# Core-ProMini.net
KiCad netlist of a schematic drawn in EAGLE
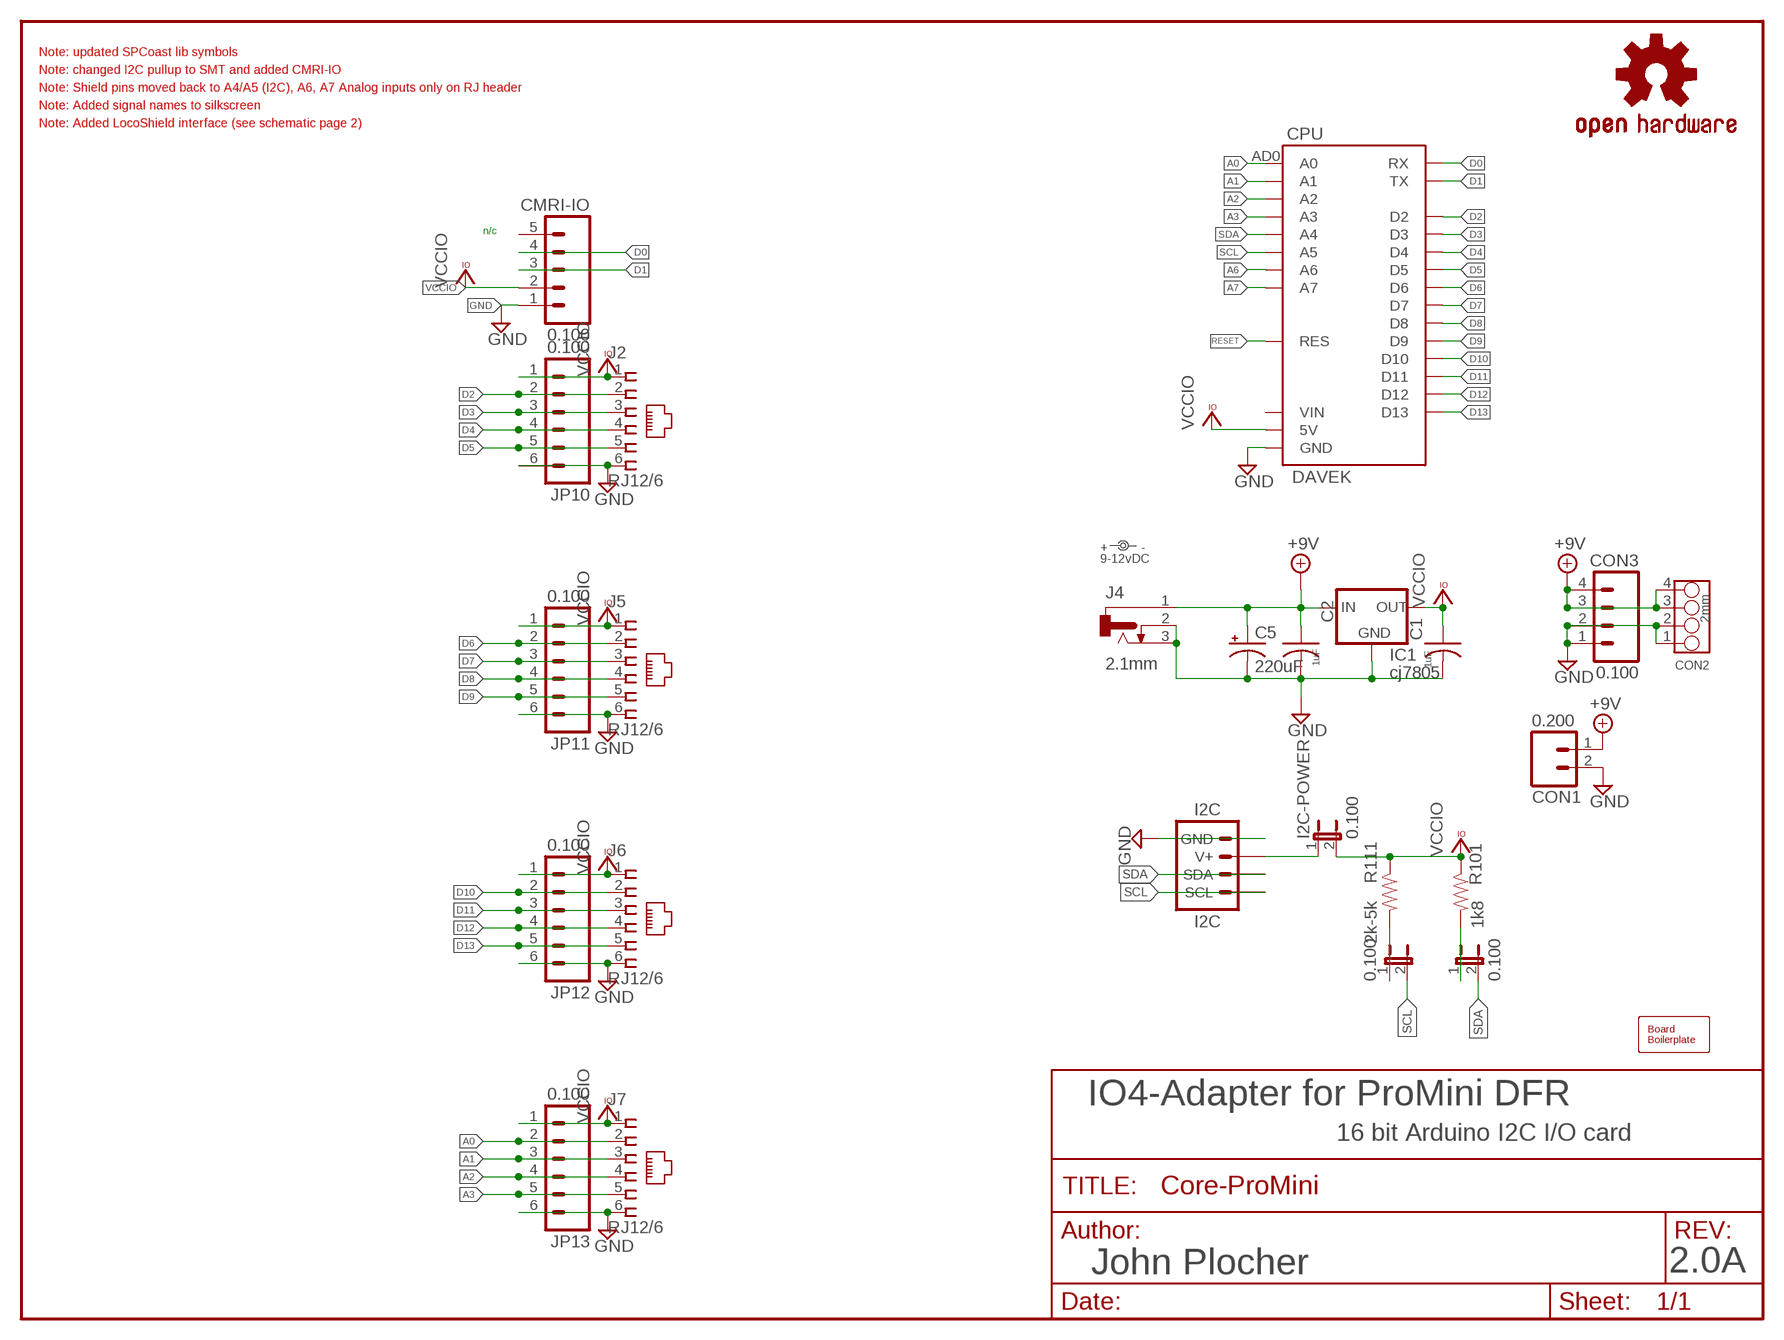
[diagram p0: schematic, sheet 1]

(export (version "E")
  (design (tool "Eeschema 10.0.6"))
  (components
    (comp (ref "BOARD")
      (value "BOARD")
      (footprint "eagle-import:BOARD-DINRAIL-3.17INX10CM")
      (libsource (lib "eagle-import") (part "BOARD80X100"))
    )
    (comp (ref "C1")
      (value "1uF")
      (footprint "eagle-import:0603-CAP")
      (libsource (lib "eagle-import") (part "CAP0603"))
    )
    (comp (ref "C2")
      (value "1uF")
      (footprint "eagle-import:0603-CAP")
      (libsource (lib "eagle-import") (part "CAP0603"))
    )
    (comp (ref "C5")
      (value "220uF")
      (footprint "eagle-import:0810-CAP")
      (libsource (lib "eagle-import") (part "CAP-POL0810"))
    )
    (comp (ref "CMRI-IO")
      (value "0.100")
      (footprint "eagle-import:1X05-CMRI-IO")
      (libsource (lib "eagle-import") (part "CONNECTOR-M05CMRI"))
    )
    (comp (ref "CON1")
      (value "0.200")
      (footprint "eagle-import:MSTB2")
      (libsource (lib "eagle-import") (part "CONNECTOR-M02508-LOCK"))
    )
    (comp (ref "CON2")
      (value "2mm")
      (footprint "eagle-import:4P-2.0")
      (libsource (lib "eagle-import") (part "CONNECTOR-GROVE-4P-2.0-3470130P1"))
    )
    (comp (ref "CON3")
      (value "0.100")
      (footprint "eagle-import:1X04_LOCK")
      (libsource (lib "eagle-import") (part "CONNECTOR-M04LOCK"))
    )
    (comp (ref "CPU")
      (value "DAVEK")
      (footprint "eagle-import:ARDUINO_PRO_MINI_DAVEK")
      (libsource (lib "eagle-import") (part "ARDUINO-PRO-MINIDAVESROBOT"))
    )
    (comp (ref "I2C")
      (value "I2C")
      (footprint "eagle-import:I2C-L")
      (libsource (lib "eagle-import") (part "CONNECTOR-I2CLEFT"))
    )
    (comp (ref "I2C-POWER")
      (value "0.100")
      (footprint "eagle-import:1X02_LOCK")
      (libsource (lib "eagle-import") (part "JUMPER-2PTH_LOCK"))
    )
    (comp (ref "IC1")
      (value "cj7805")
      (footprint "eagle-import:TO-252")
      (libsource (lib "eagle-import") (part "VREG-?-DPAK5"))
    )
    (comp (ref "J2")
      (value "RJ12/6")
      (footprint "eagle-import:RJ25-PANEL")
      (libsource (lib "eagle-import") (part "CONNECTOR-RJ25-6P6C"))
    )
    (comp (ref "J4")
      (value "2.1mm")
      (footprint "eagle-import:DCJ0202")
      (libsource (lib "eagle-import") (part "CONNECTOR-DC-POWER-RA"))
    )
    (comp (ref "J5")
      (value "RJ12/6")
      (footprint "eagle-import:RJ25-PANEL")
      (libsource (lib "eagle-import") (part "CONNECTOR-RJ25-6P6C"))
    )
    (comp (ref "J6")
      (value "RJ12/6")
      (footprint "eagle-import:RJ25-PANEL")
      (libsource (lib "eagle-import") (part "CONNECTOR-RJ25-6P6C"))
    )
    (comp (ref "J7")
      (value "RJ12/6")
      (footprint "eagle-import:RJ25-PANEL")
      (libsource (lib "eagle-import") (part "CONNECTOR-RJ25-6P6C"))
    )
    (comp (ref "JP10")
      (value "0.100")
      (footprint "eagle-import:1X06_LOCK")
      (libsource (lib "eagle-import") (part "CONNECTOR-M06LOCK"))
    )
    (comp (ref "JP11")
      (value "0.100")
      (footprint "eagle-import:1X06_LOCK")
      (libsource (lib "eagle-import") (part "CONNECTOR-M06LOCK"))
    )
    (comp (ref "JP12")
      (value "0.100")
      (footprint "eagle-import:1X06_LOCK")
      (libsource (lib "eagle-import") (part "CONNECTOR-M06LOCK"))
    )
    (comp (ref "JP13")
      (value "0.100")
      (footprint "eagle-import:1X06_LOCK")
      (libsource (lib "eagle-import") (part "CONNECTOR-M06LOCK"))
    )
    (comp (ref "OSH")
      (value "OSHW")
      (footprint "eagle-import:OSHW-LOGO-L")
      (libsource (lib "eagle-import") (part "OSHW-LOGOL"))
    )
    (comp (ref "PWR")
      (value "9-12vDC")
      (footprint "eagle-import:PWR_LABEL")
      (libsource (lib "eagle-import") (part "DOC-POWER_LABEL"))
    )
    (comp (ref "R101")
      (value "1k8")
      (footprint "eagle-import:0603-RES")
      (libsource (lib "eagle-import") (part "R0603-RES"))
    )
    (comp (ref "R111")
      (value "2k-5k")
      (footprint "eagle-import:0603-RES")
      (libsource (lib "eagle-import") (part "R0603-RES"))
    )
    (comp (ref "SCL")
      (value "0.100")
      (footprint "eagle-import:1X02_LOCK")
      (libsource (lib "eagle-import") (part "JUMPER-2PTH_LOCK"))
    )
    (comp (ref "SDA")
      (value "0.100")
      (footprint "eagle-import:1X02_LOCK")
      (libsource (lib "eagle-import") (part "JUMPER-2PTH_LOCK"))
    )
  )
  (nets
    (net (code "1") (name "+9V") (class "Default")
      (node (ref "C2") (pin "1") (pinfunction "1_1") (pintype "passive"))
      (node (ref "C5") (pin "+") (pinfunction "+_+") (pintype "passive"))
      (node (ref "CON1") (pin "1") (pinfunction "A_1") (pintype "passive"))
      (node (ref "CON2") (pin "3") (pinfunction "3_3") (pintype "bidirectional"))
      (node (ref "CON2") (pin "4") (pinfunction "4_4") (pintype "bidirectional"))
      (node (ref "CON3") (pin "3") (pinfunction "3_3") (pintype "passive"))
      (node (ref "CON3") (pin "4") (pinfunction "4_4") (pintype "passive"))
      (node (ref "IC1") (pin "1") (pinfunction "IN_1") (pintype "input"))
      (node (ref "J4") (pin "1") (pinfunction "1_1") (pintype "passive"))
    )
    (net (code "2") (name "A0") (class "Default")
      (node (ref "CPU") (pin "AD0") (pinfunction "A0_AD0") (pintype "bidirectional"))
      (node (ref "J7") (pin "2") (pinfunction "2_2") (pintype "passive"))
      (node (ref "JP13") (pin "2") (pinfunction "2_2") (pintype "passive"))
    )
    (net (code "3") (name "A1") (class "Default")
      (node (ref "CPU") (pin "AD1") (pinfunction "A1_AD1") (pintype "bidirectional"))
      (node (ref "J7") (pin "3") (pinfunction "3_3") (pintype "passive"))
      (node (ref "JP13") (pin "3") (pinfunction "3_3") (pintype "passive"))
    )
    (net (code "4") (name "A2") (class "Default")
      (node (ref "CPU") (pin "AD2") (pinfunction "A2_AD2") (pintype "bidirectional"))
      (node (ref "J7") (pin "4") (pinfunction "4_4") (pintype "passive"))
      (node (ref "JP13") (pin "4") (pinfunction "4_4") (pintype "passive"))
    )
    (net (code "5") (name "A3") (class "Default")
      (node (ref "CPU") (pin "AD3") (pinfunction "A3_AD3") (pintype "bidirectional"))
      (node (ref "J7") (pin "5") (pinfunction "5_5") (pintype "passive"))
      (node (ref "JP13") (pin "5") (pinfunction "5_5") (pintype "passive"))
    )
    (net (code "6") (name "A6") (class "Default")
      (node (ref "CPU") (pin "AD6") (pinfunction "A6_AD6") (pintype "bidirectional"))
    )
    (net (code "7") (name "A7") (class "Default")
      (node (ref "CPU") (pin "AD7") (pinfunction "A7_AD7") (pintype "bidirectional"))
    )
    (net (code "8") (name "D0") (class "Default")
      (node (ref "CMRI-IO") (pin "4") (pinfunction "4_4") (pintype "passive"))
      (node (ref "CPU") (pin "RX") (pinfunction "RX_RX") (pintype "bidirectional"))
    )
    (net (code "9") (name "D1") (class "Default")
      (node (ref "CMRI-IO") (pin "3") (pinfunction "3_3") (pintype "passive"))
      (node (ref "CPU") (pin "TX@1") (pinfunction "TX_TX@1") (pintype "bidirectional"))
    )
    (net (code "10") (name "D2") (class "Default")
      (node (ref "CPU") (pin "D2") (pinfunction "D2_D2") (pintype "bidirectional"))
      (node (ref "J2") (pin "2") (pinfunction "2_2") (pintype "passive"))
      (node (ref "JP10") (pin "2") (pinfunction "2_2") (pintype "passive"))
    )
    (net (code "11") (name "D3") (class "Default")
      (node (ref "CPU") (pin "D3") (pinfunction "D3_D3") (pintype "bidirectional"))
      (node (ref "J2") (pin "3") (pinfunction "3_3") (pintype "passive"))
      (node (ref "JP10") (pin "3") (pinfunction "3_3") (pintype "passive"))
    )
    (net (code "12") (name "D4") (class "Default")
      (node (ref "CPU") (pin "D4") (pinfunction "D4_D4") (pintype "bidirectional"))
      (node (ref "J2") (pin "4") (pinfunction "4_4") (pintype "passive"))
      (node (ref "JP10") (pin "4") (pinfunction "4_4") (pintype "passive"))
    )
    (net (code "13") (name "D5") (class "Default")
      (node (ref "CPU") (pin "D5") (pinfunction "D5_D5") (pintype "bidirectional"))
      (node (ref "J2") (pin "5") (pinfunction "5_5") (pintype "passive"))
      (node (ref "JP10") (pin "5") (pinfunction "5_5") (pintype "passive"))
    )
    (net (code "14") (name "D6") (class "Default")
      (node (ref "CPU") (pin "D6") (pinfunction "D6_D6") (pintype "bidirectional"))
      (node (ref "J5") (pin "2") (pinfunction "2_2") (pintype "passive"))
      (node (ref "JP11") (pin "2") (pinfunction "2_2") (pintype "passive"))
    )
    (net (code "15") (name "D7") (class "Default")
      (node (ref "CPU") (pin "D7") (pinfunction "D7_D7") (pintype "bidirectional"))
      (node (ref "J5") (pin "3") (pinfunction "3_3") (pintype "passive"))
      (node (ref "JP11") (pin "3") (pinfunction "3_3") (pintype "passive"))
    )
    (net (code "16") (name "D8") (class "Default")
      (node (ref "CPU") (pin "D8") (pinfunction "D8_D8") (pintype "bidirectional"))
      (node (ref "J5") (pin "4") (pinfunction "4_4") (pintype "passive"))
      (node (ref "JP11") (pin "4") (pinfunction "4_4") (pintype "passive"))
    )
    (net (code "17") (name "D9") (class "Default")
      (node (ref "CPU") (pin "D9") (pinfunction "D9_D9") (pintype "bidirectional"))
      (node (ref "J5") (pin "5") (pinfunction "5_5") (pintype "passive"))
      (node (ref "JP11") (pin "5") (pinfunction "5_5") (pintype "passive"))
    )
    (net (code "18") (name "D10") (class "Default")
      (node (ref "CPU") (pin "D10") (pinfunction "D10_D10") (pintype "bidirectional"))
      (node (ref "J6") (pin "2") (pinfunction "2_2") (pintype "passive"))
      (node (ref "JP12") (pin "2") (pinfunction "2_2") (pintype "passive"))
    )
    (net (code "19") (name "D11") (class "Default")
      (node (ref "CPU") (pin "D11") (pinfunction "D11_D11") (pintype "bidirectional"))
      (node (ref "J6") (pin "3") (pinfunction "3_3") (pintype "passive"))
      (node (ref "JP12") (pin "3") (pinfunction "3_3") (pintype "passive"))
    )
    (net (code "20") (name "D12") (class "Default")
      (node (ref "CPU") (pin "D12") (pinfunction "D12_D12") (pintype "bidirectional"))
      (node (ref "J6") (pin "4") (pinfunction "4_4") (pintype "passive"))
      (node (ref "JP12") (pin "4") (pinfunction "4_4") (pintype "passive"))
    )
    (net (code "21") (name "D13") (class "Default")
      (node (ref "CPU") (pin "D13") (pinfunction "D13_D13") (pintype "bidirectional"))
      (node (ref "J6") (pin "5") (pinfunction "5_5") (pintype "passive"))
      (node (ref "JP12") (pin "5") (pinfunction "5_5") (pintype "passive"))
    )
    (net (code "22") (name "GND") (class "Default")
      (node (ref "C1") (pin "2") (pinfunction "2_2") (pintype "passive"))
      (node (ref "C2") (pin "2") (pinfunction "2_2") (pintype "passive"))
      (node (ref "C5") (pin "-") (pinfunction "-_-") (pintype "passive"))
      (node (ref "CMRI-IO") (pin "1") (pinfunction "1_1") (pintype "passive"))
      (node (ref "CON1") (pin "2") (pinfunction "B_2") (pintype "passive"))
      (node (ref "CON2") (pin "1") (pinfunction "1_1") (pintype "bidirectional"))
      (node (ref "CON2") (pin "2") (pinfunction "2_2") (pintype "bidirectional"))
      (node (ref "CON3") (pin "1") (pinfunction "1_1") (pintype "passive"))
      (node (ref "CON3") (pin "2") (pinfunction "2_2") (pintype "passive"))
      (node (ref "CPU") (pin "GND@1") (pinfunction "GND_GND@1") (pintype "bidirectional"))
      (node (ref "CPU") (pin "GND@2") (pinfunction "GND_GND@2") (pintype "bidirectional"))
      (node (ref "CPU") (pin "GND@4") (pinfunction "GND_GND@4") (pintype "bidirectional"))
      (node (ref "I2C") (pin "GND") (pinfunction "GND_GND") (pintype "passive"))
      (node (ref "I2C") (pin "GND@1") (pinfunction "GND_GND@1") (pintype "passive"))
      (node (ref "IC1") (pin "2") (pinfunction "GND_2") (pintype "input"))
      (node (ref "J2") (pin "6") (pinfunction "6_6") (pintype "passive"))
      (node (ref "J4") (pin "2") (pinfunction "2_2") (pintype "passive"))
      (node (ref "J4") (pin "3") (pinfunction "3_3") (pintype "passive"))
      (node (ref "J5") (pin "6") (pinfunction "6_6") (pintype "passive"))
      (node (ref "J6") (pin "6") (pinfunction "6_6") (pintype "passive"))
      (node (ref "J7") (pin "6") (pinfunction "6_6") (pintype "passive"))
      (node (ref "JP10") (pin "6") (pinfunction "6_6") (pintype "passive"))
      (node (ref "JP11") (pin "6") (pinfunction "6_6") (pintype "passive"))
      (node (ref "JP12") (pin "6") (pinfunction "6_6") (pintype "passive"))
      (node (ref "JP13") (pin "6") (pinfunction "6_6") (pintype "passive"))
    )
    (net (code "23") (name "Net-(I2C-POWER-Pad1)") (class "Default")
      (node (ref "I2C") (pin "V+") (pinfunction "V+_V+") (pintype "passive"))
      (node (ref "I2C") (pin "V+@1") (pinfunction "V+_V+@1") (pintype "passive"))
      (node (ref "I2C-POWER") (pin "1") (pinfunction "1_1") (pintype "passive"))
    )
    (net (code "24") (name "Net-(R101-Pad2)") (class "Default")
      (node (ref "R101") (pin "2") (pinfunction "2_2") (pintype "passive"))
      (node (ref "SDA") (pin "1") (pinfunction "1_1") (pintype "passive"))
    )
    (net (code "25") (name "Net-(R111-Pad2)") (class "Default")
      (node (ref "R111") (pin "2") (pinfunction "2_2") (pintype "passive"))
      (node (ref "SCL") (pin "1") (pinfunction "1_1") (pintype "passive"))
    )
    (net (code "26") (name "RESET") (class "Default")
      (node (ref "CPU") (pin "RES") (pinfunction "RES_RES") (pintype "bidirectional"))
      (node (ref "CPU") (pin "RES@1") (pinfunction "RES_RES@1") (pintype "bidirectional"))
    )
    (net (code "27") (name "SCL") (class "Default")
      (node (ref "CPU") (pin "AD5") (pinfunction "A5_AD5") (pintype "bidirectional"))
      (node (ref "I2C") (pin "SCL") (pinfunction "SCL_SCL") (pintype "passive"))
      (node (ref "I2C") (pin "SCL@1") (pinfunction "SCL_SCL@1") (pintype "passive"))
      (node (ref "SCL") (pin "2") (pinfunction "2_2") (pintype "passive"))
    )
    (net (code "28") (name "SDA") (class "Default")
      (node (ref "CPU") (pin "AD4") (pinfunction "A4_AD4") (pintype "bidirectional"))
      (node (ref "I2C") (pin "SDA") (pinfunction "SDA_SDA") (pintype "passive"))
      (node (ref "I2C") (pin "SDA@1") (pinfunction "SDA_SDA@1") (pintype "passive"))
      (node (ref "SDA") (pin "2") (pinfunction "2_2") (pintype "passive"))
    )
    (net (code "29") (name "VCCIO") (class "Default")
      (node (ref "C1") (pin "1") (pinfunction "1_1") (pintype "passive"))
      (node (ref "CMRI-IO") (pin "2") (pinfunction "2_2") (pintype "passive"))
      (node (ref "CPU") (pin "5V") (pinfunction "5V_5V") (pintype "bidirectional"))
      (node (ref "I2C-POWER") (pin "2") (pinfunction "2_2") (pintype "passive"))
      (node (ref "IC1") (pin "3") (pinfunction "OUT_3") (pintype "output"))
      (node (ref "J2") (pin "1") (pinfunction "1_1") (pintype "passive"))
      (node (ref "J5") (pin "1") (pinfunction "1_1") (pintype "passive"))
      (node (ref "J6") (pin "1") (pinfunction "1_1") (pintype "passive"))
      (node (ref "J7") (pin "1") (pinfunction "1_1") (pintype "passive"))
      (node (ref "JP10") (pin "1") (pinfunction "1_1") (pintype "passive"))
      (node (ref "JP11") (pin "1") (pinfunction "1_1") (pintype "passive"))
      (node (ref "JP12") (pin "1") (pinfunction "1_1") (pintype "passive"))
      (node (ref "JP13") (pin "1") (pinfunction "1_1") (pintype "passive"))
      (node (ref "R101") (pin "1") (pinfunction "1_1") (pintype "passive"))
      (node (ref "R111") (pin "1") (pinfunction "1_1") (pintype "passive"))
    )
    (net (code "30") (name "unconnected-(CMRI-IO-Pad5)") (class "Default")
      (node (ref "CMRI-IO") (pin "5") (pinfunction "5_5") (pintype "passive"))
    )
    (net (code "31") (name "unconnected-(CPU-PadVIN)") (class "Default")
      (node (ref "CPU") (pin "VIN") (pinfunction "VIN_VIN") (pintype "bidirectional"))
    )
  )
)
